# Cuurent_Monitored_Power_Switch.net
KiCad netlist of a schematic drawn in Altium Designer
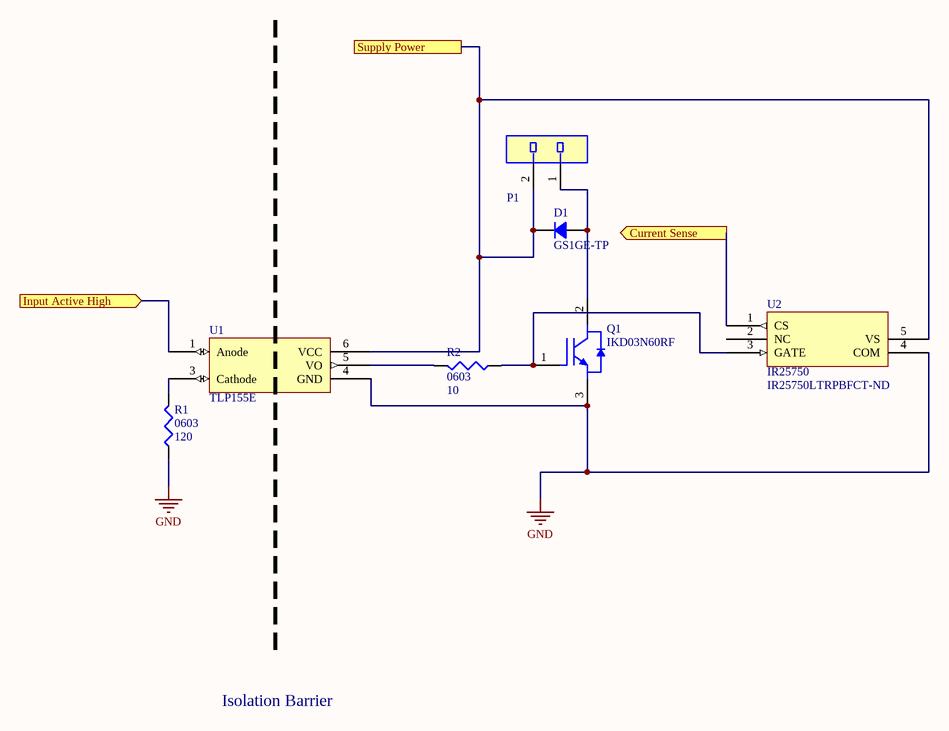
[diagram p0: Cuurent Monitored Power Switch.SchDoc]

(export (version "E")
  (design (tool "Eeschema 10.0.6"))
  (components
    (comp (ref "D1")
      (value "GS1GE-TP")
      (footprint "DO214AC SMA")
      (description "Diode Switching 400V 1A 2-Pin SMAE T/R")
      (fields (field (name "MANUFACTURER") "MCC"))
      (libsource (lib "Main Library") (part "Diode"))
    )
    (comp (ref "P1")
      (value "70553-0001")
      (footprint "Molex_70553-0001_MFG")
      (description "24V power in")
      (libsource (lib "Main Library") (part "70553-0001"))
    )
    (comp (ref "Q1")
      (value "IKD03N60RF")
      (footprint "INF-PG-TO252-3-21_V")
      (fields (field (name "MANUFACTURER") "Infineon"))
      (libsource (lib "Altium Content Vault") (part "INF-IXXXXXXX-PG-TO220_247-3_1"))
    )
    (comp (ref "R1")
      (value "0603")
      (footprint "J1-0603")
      (description "Resistor")
      (fields (field (name "ALTIUM_VALUE") "120") (field (name "PUBLISHER") "Altium Limited"))
      (libsource (lib "Miscellaneous Devices") (part "Res3"))
    )
    (comp (ref "R2")
      (value "0603")
      (footprint "J1-0603")
      (description "Resistor")
      (fields (field (name "ALTIUM_VALUE") "10") (field (name "PUBLISHER") "Altium Limited"))
      (libsource (lib "Miscellaneous Devices") (part "Res3"))
    )
    (comp (ref "U1")
      (value "TLP155E")
      (footprint "TB-SO6-5")
      (description "Logic gate drive optocoupler 7.5mA input threshold .6A peak output current 10V-30V output supply")
      (libsource (lib "Main Library") (part "TLP155E"))
    )
    (comp (ref "U2")
      (value "IR25750")
      (footprint "SOT23-5")
      (description "1.8V/2.5V/3.3V/5V/9V/12V/15V/18V/24V 5-Pin SOT-23 T/R")
      (fields
        (field (name "MANUFACTURER") "International Rectifier")
        (field (name "MANUFACTURER PART NUMBER") "IR25750LTRPBF")
        (field (name "SUPPLIER PART NUMBER 1") "IR25750LTRPBFCT-ND")
      )
      (libsource (lib "Main Library") (part "IR25750"))
    )
  )
  (nets
    (net (code "1") (name "/Current Sense") (class "Default")
      (node (ref "U2") (pin "1") (pinfunction "CS_1") (pintype "output"))
    )
    (net (code "2") (name "/Input Active High") (class "Default")
      (node (ref "U1") (pin "1") (pinfunction "Anode_1") (pintype "bidirectional"))
    )
    (net (code "3") (name "/Supply Power") (class "Default")
      (node (ref "D1") (pin "2") (pinfunction "2_2") (pintype "passive"))
      (node (ref "P1") (pin "2") (pinfunction "2_2") (pintype "passive"))
      (node (ref "U1") (pin "6") (pinfunction "VCC_6") (pintype "power_in"))
      (node (ref "U2") (pin "5") (pinfunction "VS_5") (pintype "power_in"))
    )
    (net (code "4") (name "GND") (class "Default")
      (node (ref "Q1") (pin "3") (pinfunction "E_3") (pintype "passive"))
      (node (ref "R1") (pin "1") (pinfunction "1_1") (pintype "passive"))
      (node (ref "U1") (pin "4") (pinfunction "GND_4") (pintype "power_in"))
      (node (ref "U2") (pin "4") (pinfunction "COM_4") (pintype "power_in"))
    )
    (net (code "5") (name "Net-(Q1-C)") (class "Default")
      (node (ref "D1") (pin "1") (pinfunction "1_1") (pintype "passive"))
      (node (ref "P1") (pin "1") (pinfunction "1_1") (pintype "passive"))
      (node (ref "Q1") (pin "2") (pinfunction "C_2") (pintype "passive"))
    )
    (net (code "6") (name "Net-(Q1-G)") (class "Default")
      (node (ref "Q1") (pin "1") (pinfunction "G_1") (pintype "passive"))
      (node (ref "R2") (pin "1") (pinfunction "1_1") (pintype "passive"))
      (node (ref "U2") (pin "3") (pinfunction "GATE_3") (pintype "input"))
    )
    (net (code "7") (name "Net-(U1-Cathode)") (class "Default")
      (node (ref "R1") (pin "2") (pinfunction "2_2") (pintype "passive"))
      (node (ref "U1") (pin "3") (pinfunction "Cathode_3") (pintype "bidirectional"))
    )
    (net (code "8") (name "Net-(U1-VO)") (class "Default")
      (node (ref "R2") (pin "2") (pinfunction "2_2") (pintype "passive"))
      (node (ref "U1") (pin "5") (pinfunction "VO_5") (pintype "output"))
    )
    (net (code "9") (name "unconnected-(U2-NC-Pad2)") (class "Default")
      (node (ref "U2") (pin "2") (pinfunction "NC_2") (pintype "passive"))
    )
  )
)
